# Esq_exemplo-pratico-1.net
KiCad netlist of a schematic drawn in EAGLE
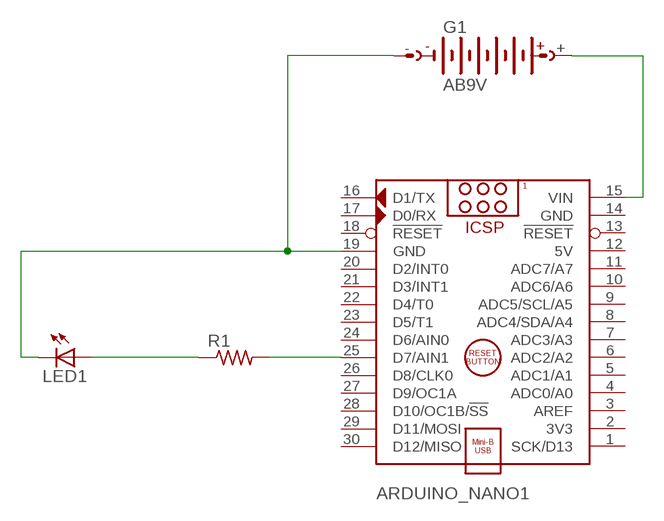
[diagram p0: schematic, sheet 1]

(export (version "E")
  (design (tool "Eeschema 10.0.6"))
  (components
    (comp (ref "ARDUINO_NANO1")
      (value "ARDUINO_NANO")
      (footprint "eagle-import:ARDUINO_NANO")
      (libsource (lib "eagle-import") (part "ARDUINO_NANO"))
    )
    (comp (ref "G1")
      (value "AB9V")
      (footprint "eagle-import:AB9V")
      (libsource (lib "eagle-import") (part "AB9V"))
    )
    (comp (ref "LED1")
      (value "LED3MM")
      (footprint "eagle-import:LED3MM")
      (libsource (lib "eagle-import") (part "LED3MM"))
    )
    (comp (ref "R1")
      (value "R-US_FLIPFLOP")
      (footprint "eagle-import:0805-THM")
      (libsource (lib "eagle-import") (part "R-US_FLIPFLOP"))
    )
  )
  (nets
    (net (code "1") (name "/5V") (class "Default")
      (node (ref "ARDUINO_NANO1") (pin "12") (pinfunction "5V_12") (pintype "power_in"))
    )
    (net (code "2") (name "/GND") (class "Default")
      (node (ref "ARDUINO_NANO1") (pin "14") (pinfunction "GND_14") (pintype "power_in"))
    )
    (net (code "3") (name "Net-(ARDUINO_NANO1-D7{slash}AIN1)") (class "Default")
      (node (ref "ARDUINO_NANO1") (pin "25") (pinfunction "D7/AIN1_25") (pintype "bidirectional"))
      (node (ref "R1") (pin "2") (pinfunction "2_2") (pintype "passive"))
    )
    (net (code "4") (name "Net-(ARDUINO_NANO1-VIN)") (class "Default")
      (node (ref "ARDUINO_NANO1") (pin "15") (pinfunction "VIN_15") (pintype "power_in"))
      (node (ref "G1") (pin "+") (pinfunction "+_+") (pintype "passive"))
    )
    (net (code "5") (name "Net-(LED1-C)") (class "Default")
      (node (ref "ARDUINO_NANO1") (pin "19") (pinfunction "GND_19") (pintype "power_in"))
      (node (ref "G1") (pin "-") (pinfunction "-_-") (pintype "passive"))
      (node (ref "LED1") (pin "K") (pinfunction "C_K") (pintype "passive"))
    )
    (net (code "6") (name "Net-(LED1-PadA)") (class "Default")
      (node (ref "LED1") (pin "A") (pinfunction "A_A") (pintype "passive"))
      (node (ref "R1") (pin "1") (pinfunction "1_1") (pintype "passive"))
    )
    (net (code "7") (name "unconnected-(ARDUINO_NANO1-3V3-Pad2)") (class "Default")
      (node (ref "ARDUINO_NANO1") (pin "2") (pinfunction "3V3_2") (pintype "output"))
    )
    (net (code "8") (name "unconnected-(ARDUINO_NANO1-ADC0{slash}A0-Pad4)") (class "Default")
      (node (ref "ARDUINO_NANO1") (pin "4") (pinfunction "ADC0/A0_4") (pintype "bidirectional"))
    )
    (net (code "9") (name "unconnected-(ARDUINO_NANO1-ADC1{slash}A1-Pad5)") (class "Default")
      (node (ref "ARDUINO_NANO1") (pin "5") (pinfunction "ADC1/A1_5") (pintype "bidirectional"))
    )
    (net (code "10") (name "unconnected-(ARDUINO_NANO1-ADC2{slash}A2-Pad6)") (class "Default")
      (node (ref "ARDUINO_NANO1") (pin "6") (pinfunction "ADC2/A2_6") (pintype "bidirectional"))
    )
    (net (code "11") (name "unconnected-(ARDUINO_NANO1-ADC3{slash}A3-Pad7)") (class "Default")
      (node (ref "ARDUINO_NANO1") (pin "7") (pinfunction "ADC3/A3_7") (pintype "bidirectional"))
    )
    (net (code "12") (name "unconnected-(ARDUINO_NANO1-ADC4{slash}SDA{slash}A4-Pad8)") (class "Default")
      (node (ref "ARDUINO_NANO1") (pin "8") (pinfunction "ADC4/SDA/A4_8") (pintype "bidirectional"))
    )
    (net (code "13") (name "unconnected-(ARDUINO_NANO1-ADC5{slash}SCL{slash}A5-Pad9)") (class "Default")
      (node (ref "ARDUINO_NANO1") (pin "9") (pinfunction "ADC5/SCL/A5_9") (pintype "bidirectional"))
    )
    (net (code "14") (name "unconnected-(ARDUINO_NANO1-ADC6{slash}A6-Pad10)") (class "Default")
      (node (ref "ARDUINO_NANO1") (pin "10") (pinfunction "ADC6/A6_10") (pintype "bidirectional"))
    )
    (net (code "15") (name "unconnected-(ARDUINO_NANO1-ADC7{slash}A7-Pad11)") (class "Default")
      (node (ref "ARDUINO_NANO1") (pin "11") (pinfunction "ADC7/A7_11") (pintype "bidirectional"))
    )
    (net (code "16") (name "unconnected-(ARDUINO_NANO1-AREF-Pad3)") (class "Default")
      (node (ref "ARDUINO_NANO1") (pin "3") (pinfunction "AREF_3") (pintype "input"))
    )
    (net (code "17") (name "unconnected-(ARDUINO_NANO1-D0{slash}RX-Pad17)") (class "Default")
      (node (ref "ARDUINO_NANO1") (pin "17") (pinfunction "D0/RX_17") (pintype "bidirectional"))
    )
    (net (code "18") (name "unconnected-(ARDUINO_NANO1-D1{slash}TX-Pad16)") (class "Default")
      (node (ref "ARDUINO_NANO1") (pin "16") (pinfunction "D1/TX_16") (pintype "bidirectional"))
    )
    (net (code "19") (name "unconnected-(ARDUINO_NANO1-D2{slash}INT0-Pad20)") (class "Default")
      (node (ref "ARDUINO_NANO1") (pin "20") (pinfunction "D2/INT0_20") (pintype "bidirectional"))
    )
    (net (code "20") (name "unconnected-(ARDUINO_NANO1-D3{slash}INT1-Pad21)") (class "Default")
      (node (ref "ARDUINO_NANO1") (pin "21") (pinfunction "D3/INT1_21") (pintype "bidirectional"))
    )
    (net (code "21") (name "unconnected-(ARDUINO_NANO1-D4{slash}T0-Pad22)") (class "Default")
      (node (ref "ARDUINO_NANO1") (pin "22") (pinfunction "D4/T0_22") (pintype "bidirectional"))
    )
    (net (code "22") (name "unconnected-(ARDUINO_NANO1-D5{slash}T1-Pad23)") (class "Default")
      (node (ref "ARDUINO_NANO1") (pin "23") (pinfunction "D5/T1_23") (pintype "bidirectional"))
    )
    (net (code "23") (name "unconnected-(ARDUINO_NANO1-D6{slash}AIN0-Pad24)") (class "Default")
      (node (ref "ARDUINO_NANO1") (pin "24") (pinfunction "D6/AIN0_24") (pintype "bidirectional"))
    )
    (net (code "24") (name "unconnected-(ARDUINO_NANO1-D8{slash}CLK0-Pad26)") (class "Default")
      (node (ref "ARDUINO_NANO1") (pin "26") (pinfunction "D8/CLK0_26") (pintype "bidirectional"))
    )
    (net (code "25") (name "unconnected-(ARDUINO_NANO1-D9{slash}OC1A-Pad27)") (class "Default")
      (node (ref "ARDUINO_NANO1") (pin "27") (pinfunction "D9/OC1A_27") (pintype "bidirectional"))
    )
    (net (code "26") (name "unconnected-(ARDUINO_NANO1-D10{slash}OC1B{slash}~{SS}-Pad28)") (class "Default")
      (node (ref "ARDUINO_NANO1") (pin "28") (pinfunction "D10/OC1B/~{SS}_28") (pintype "bidirectional"))
    )
    (net (code "27") (name "unconnected-(ARDUINO_NANO1-D11{slash}MOSI-Pad29)") (class "Default")
      (node (ref "ARDUINO_NANO1") (pin "29") (pinfunction "D11/MOSI_29") (pintype "bidirectional"))
    )
    (net (code "28") (name "unconnected-(ARDUINO_NANO1-D12{slash}MISO-Pad30)") (class "Default")
      (node (ref "ARDUINO_NANO1") (pin "30") (pinfunction "D12/MISO_30") (pintype "bidirectional"))
    )
    (net (code "29") (name "unconnected-(ARDUINO_NANO1-SCK{slash}D13-Pad1)") (class "Default")
      (node (ref "ARDUINO_NANO1") (pin "1") (pinfunction "SCK/D13_1") (pintype "bidirectional"))
    )
    (net (code "30") (name "unconnected-(ARDUINO_NANO1-~{RESET}-Pad13)") (class "Default")
      (node (ref "ARDUINO_NANO1") (pin "13") (pinfunction "~{RESET}_13") (pintype "input"))
    )
    (net (code "31") (name "unconnected-(ARDUINO_NANO1-~{RESET}-Pad18)") (class "Default")
      (node (ref "ARDUINO_NANO1") (pin "18") (pinfunction "~{RESET}_18") (pintype "input"))
    )
  )
)
